# SIM.net
KiCad netlist of a schematic drawn in Altium Designer
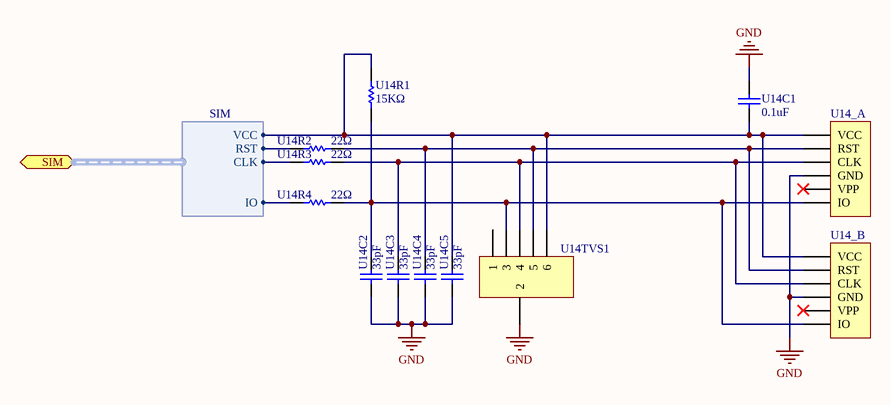
[diagram p0: SIM.SchDoc]

(export (version "E")
  (design (tool "Eeschema 10.0.6"))
  (components
    (comp (ref "U14C1")
      (value "0.1uF")
      (footprint "0603 - CAP")
      (description "CAP CERAMIC 0.1UF, 25V, X7R, 0603")
      (fields
        (field (name "MANUFACTURER PART NUMBER") "CGJ3E2X7R1E104K080AA")
        (field (name "MANUFACTURER") "TDK Corporation")
      )
      (libsource (lib "*") (part "Cap"))
    )
    (comp (ref "U14C2")
      (value "33pF")
      (footprint "0805-cap")
      (description "33pF 50V Ceramic Capacitor C0G, NP0 0805 (2012 Metric) 0.079\" L x 0.049\" W (2.00mm x 1.25mm)")
      (fields
        (field (name "MANUFACTURER") "Kemet")
        (field (name "MANUFACTURER PART NUMBER") "C0805C330J5GACTU")
      )
      (libsource (lib "LibreriaEstandar2") (part "Cap"))
    )
    (comp (ref "U14C3")
      (value "33pF")
      (footprint "0805-cap")
      (description "33pF 50V Ceramic Capacitor C0G, NP0 0805 (2012 Metric) 0.079\" L x 0.049\" W (2.00mm x 1.25mm)")
      (fields
        (field (name "MANUFACTURER") "Kemet")
        (field (name "MANUFACTURER PART NUMBER") "C0805C330J5GACTU")
      )
      (libsource (lib "LibreriaEstandar2") (part "Cap"))
    )
    (comp (ref "U14C4")
      (value "33pF")
      (footprint "0805-cap")
      (description "33pF 50V Ceramic Capacitor C0G, NP0 0805 (2012 Metric) 0.079\" L x 0.049\" W (2.00mm x 1.25mm)")
      (fields
        (field (name "MANUFACTURER") "Kemet")
        (field (name "MANUFACTURER PART NUMBER") "C0805C330J5GACTU")
      )
      (libsource (lib "LibreriaEstandar2") (part "Cap"))
    )
    (comp (ref "U14C5")
      (value "33pF")
      (footprint "0805-cap")
      (description "33pF 50V Ceramic Capacitor C0G, NP0 0805 (2012 Metric) 0.079\" L x 0.049\" W (2.00mm x 1.25mm)")
      (fields
        (field (name "MANUFACTURER") "Kemet")
        (field (name "MANUFACTURER PART NUMBER") "C0805C330J5GACTU")
      )
      (libsource (lib "LibreriaEstandar2") (part "Cap"))
    )
    (comp (ref "U14R1")
      (value "15KΩ")
      (footprint "0805-RES")
      (description "RES SMD 15K OHM 1% 1/8W 0805")
      (fields
        (field (name "MANUFACTURER") "Panasonic Electronic Components")
        (field (name "MANUFACTURER PART NUMBER") "ERJ-6ENF1502V")
      )
      (libsource (lib "Miscellaneous Devices") (part "Res1"))
    )
    (comp (ref "U14R2")
      (value "22Ω")
      (footprint "0805-RES")
      (description "RES SMD 22 OHM 1% 1/8W 0805")
      (fields
        (field (name "MANUFACTURER") "Panasonic Electronic Components")
        (field (name "MANUFACTURER PART NUMBER") "ERJ-6ENF22R0V")
      )
      (libsource (lib "Miscellaneous Devices") (part "Res1"))
    )
    (comp (ref "U14R3")
      (value "22Ω")
      (footprint "0805-RES")
      (description "RES SMD 22 OHM 1% 1/8W 0805")
      (fields
        (field (name "MANUFACTURER") "Panasonic Electronic Components")
        (field (name "MANUFACTURER PART NUMBER") "ERJ-6ENF22R0V")
      )
      (libsource (lib "Miscellaneous Devices") (part "Res1"))
    )
    (comp (ref "U14R4")
      (value "22Ω")
      (footprint "0805-RES")
      (description "RES SMD 22 OHM 1% 1/8W 0805")
      (fields
        (field (name "MANUFACTURER") "Panasonic Electronic Components")
        (field (name "MANUFACTURER PART NUMBER") "ERJ-6ENF22R0V")
      )
      (libsource (lib "Miscellaneous Devices") (part "Res1"))
    )
    (comp (ref "U14TVS1")
      (value "SMF05C.TCT")
      (footprint "SC70-6")
      (description "TVS DIODE 5V 12.5V SC70-6")
      (fields (field (name "MANUFACTURER") "Semtech Corporation"))
      (libsource (lib "Miscellaneous Connectors") (part "Header 6"))
    )
    (comp (ref "U14_A")
      (value "0786463001")
      (footprint "0786463001-SIM")
      (description "'6 Position Card Connector Micro SIM Surface Mount, Right Angle Gold")
      (fields (field (name "MANUFACTURER") "Molex, LLC"))
      (libsource (lib "") (part "Header 6_1"))
    )
    (comp (ref "U14_B")
      (value "7111S2015X02LF")
      (footprint "SIM-6")
      (description "6 Position Card Connector SIM Card Surface Mount, Right Angle Gold")
      (fields (field (name "MANUFACTURER") "Amphenol FCI"))
      (libsource (lib "") (part "Header 6_1"))
    )
  )
  (nets
    (net (code "2") (name "/CLK") (class "Default")
      (node (ref "U14R3") (pin "1") (pinfunction "1_1") (pintype "passive"))
    )
    (net (code "3") (name "/IO") (class "Default")
      (node (ref "U14R4") (pin "1") (pinfunction "1_1") (pintype "passive"))
    )
    (net (code "4") (name "/RST") (class "Default")
      (node (ref "U14R2") (pin "1") (pinfunction "1_1") (pintype "passive"))
    )
    (net (code "5") (name "/VCC") (class "Default")
      (node (ref "U14C1") (pin "1") (pinfunction "1_1") (pintype "passive"))
      (node (ref "U14C5") (pin "2") (pinfunction "2_2") (pintype "passive"))
      (node (ref "U14R1") (pin "1") (pinfunction "1_1") (pintype "passive"))
      (node (ref "U14TVS1") (pin "6") (pinfunction "6_6") (pintype "passive"))
      (node (ref "U14_A") (pin "1") (pinfunction "VCC_1") (pintype "passive"))
      (node (ref "U14_B") (pin "1") (pinfunction "VCC_1") (pintype "passive"))
    )
    (net (code "7") (name "GND") (class "Default")
      (node (ref "U14C1") (pin "2") (pinfunction "2_2") (pintype "passive"))
      (node (ref "U14C2") (pin "1") (pinfunction "1_1") (pintype "passive"))
      (node (ref "U14C3") (pin "1") (pinfunction "1_1") (pintype "passive"))
      (node (ref "U14C4") (pin "1") (pinfunction "1_1") (pintype "passive"))
      (node (ref "U14C5") (pin "1") (pinfunction "1_1") (pintype "passive"))
      (node (ref "U14TVS1") (pin "2") (pinfunction "2_2") (pintype "passive"))
      (node (ref "U14_A") (pin "5") (pinfunction "GND_5") (pintype "passive"))
      (node (ref "U14_B") (pin "5") (pinfunction "GND_5") (pintype "passive"))
    )
    (net (code "8") (name "Net-(U14_A-CLK)") (class "Default")
      (node (ref "U14C3") (pin "2") (pinfunction "2_2") (pintype "passive"))
      (node (ref "U14R3") (pin "2") (pinfunction "2_2") (pintype "passive"))
      (node (ref "U14TVS1") (pin "4") (pinfunction "4_4") (pintype "passive"))
      (node (ref "U14_A") (pin "3") (pinfunction "CLK_3") (pintype "passive"))
      (node (ref "U14_B") (pin "3") (pinfunction "CLK_3") (pintype "passive"))
    )
    (net (code "9") (name "Net-(U14_A-IO)") (class "Default")
      (node (ref "U14C2") (pin "2") (pinfunction "2_2") (pintype "passive"))
      (node (ref "U14R1") (pin "2") (pinfunction "2_2") (pintype "passive"))
      (node (ref "U14R4") (pin "2") (pinfunction "2_2") (pintype "passive"))
      (node (ref "U14TVS1") (pin "3") (pinfunction "3_3") (pintype "passive"))
      (node (ref "U14_A") (pin "7") (pinfunction "IO_7") (pintype "passive"))
      (node (ref "U14_B") (pin "7") (pinfunction "IO_7") (pintype "passive"))
    )
    (net (code "10") (name "Net-(U14_A-RST)") (class "Default")
      (node (ref "U14C4") (pin "2") (pinfunction "2_2") (pintype "passive"))
      (node (ref "U14R2") (pin "2") (pinfunction "2_2") (pintype "passive"))
      (node (ref "U14TVS1") (pin "5") (pinfunction "5_5") (pintype "passive"))
      (node (ref "U14_A") (pin "2") (pinfunction "RST_2") (pintype "passive"))
      (node (ref "U14_B") (pin "2") (pinfunction "RST_2") (pintype "passive"))
    )
    (net (code "11") (name "unconnected-(U14TVS1-Pad1)") (class "Default")
      (node (ref "U14TVS1") (pin "1") (pinfunction "1_1") (pintype "passive"))
    )
    (net (code "12") (name "unconnected-(U14_A-VPP-Pad6)") (class "Default")
      (node (ref "U14_A") (pin "6") (pinfunction "VPP_6") (pintype "passive+no_connect"))
    )
    (net (code "13") (name "unconnected-(U14_B-VPP-Pad6)") (class "Default")
      (node (ref "U14_B") (pin "6") (pinfunction "VPP_6") (pintype "passive+no_connect"))
    )
  )
)
